# TSEM_R2.net
KiCad netlist of a schematic drawn in EAGLE
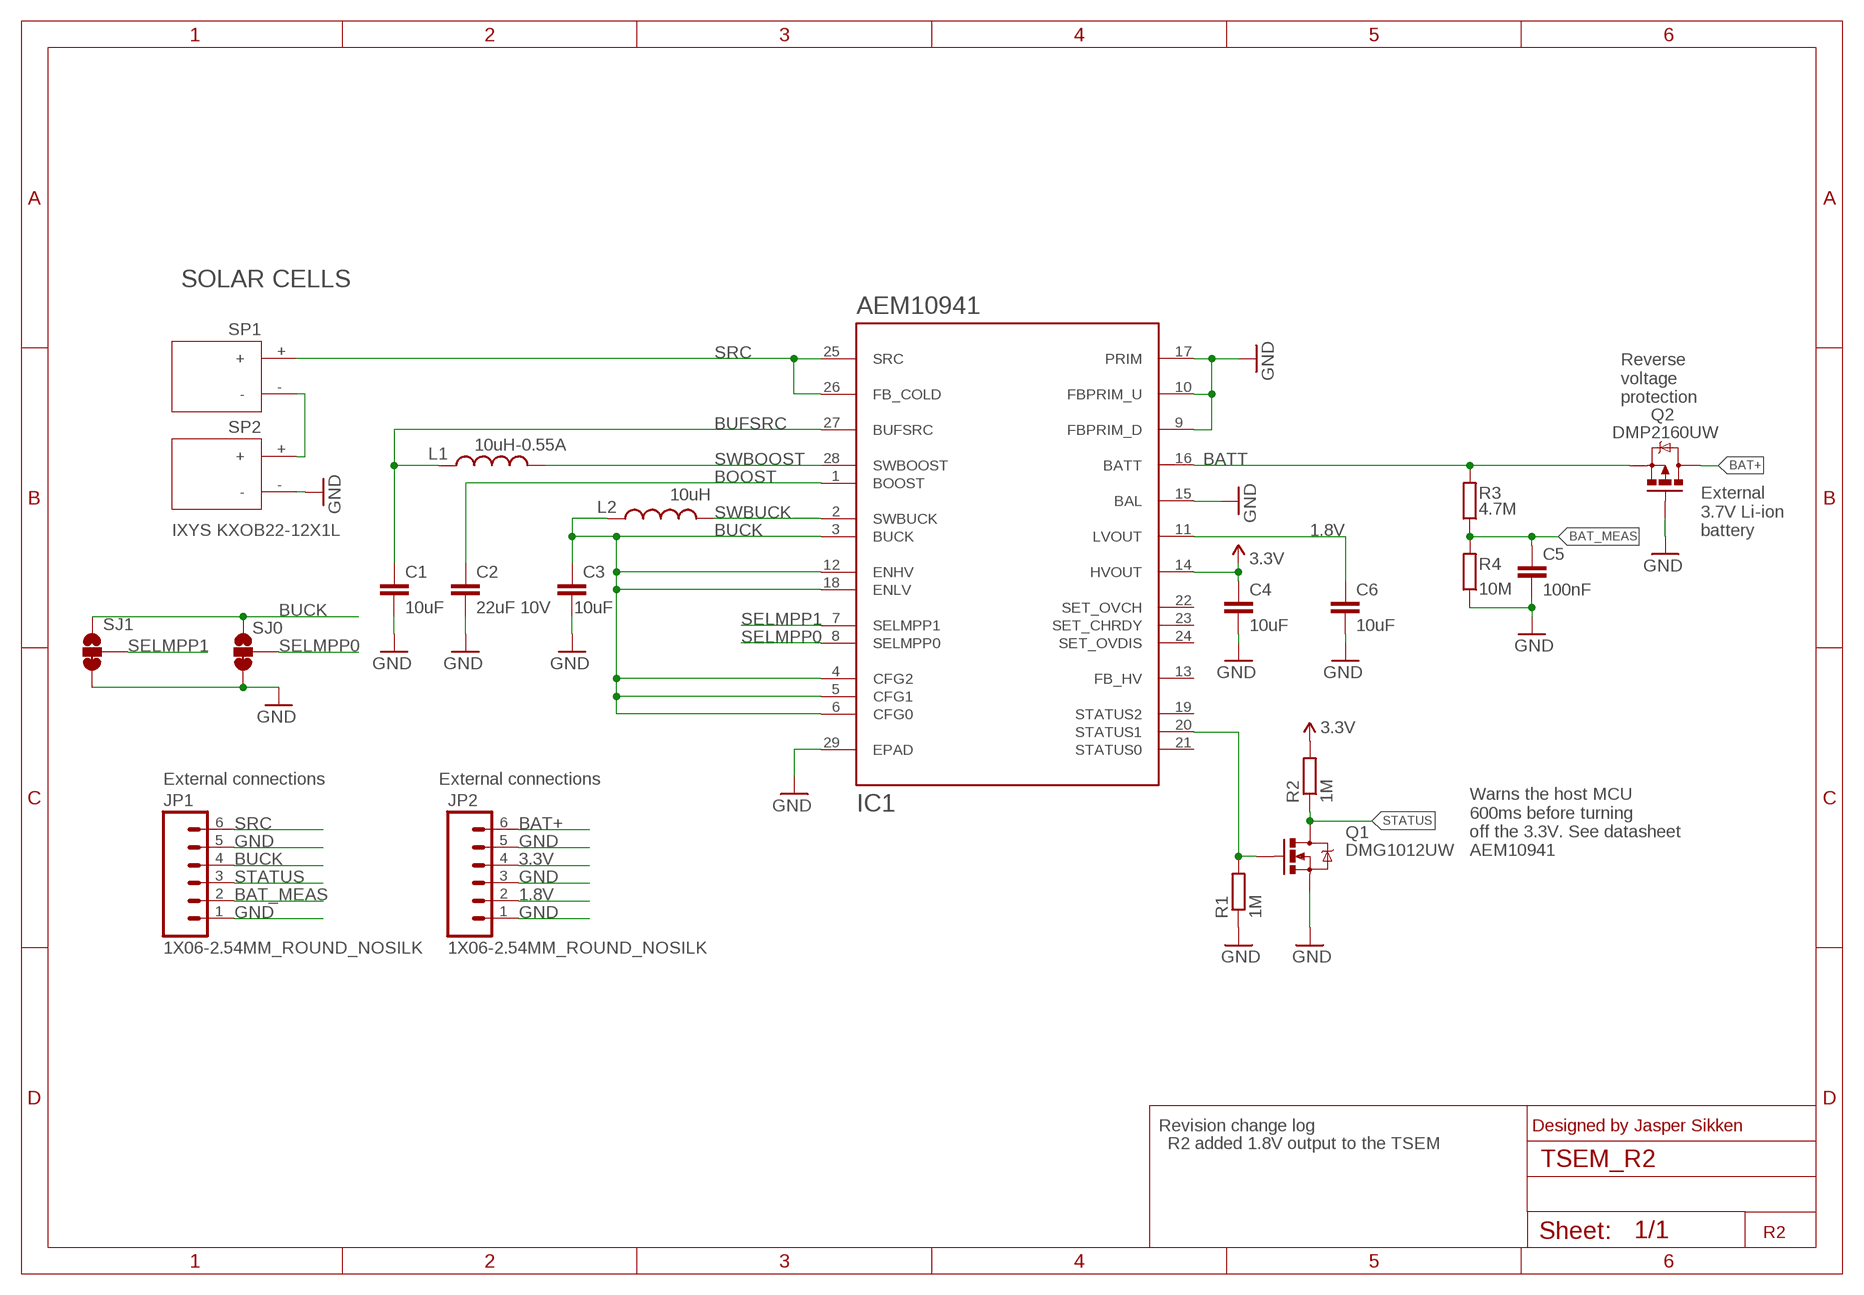
[diagram p0: schematic, sheet 1]

(export (version "E")
  (design (tool "Eeschema 10.0.6"))
  (components
    (comp (ref "C1")
      (value "10uF")
      (footprint "eagle-import:C0603")
      (fields (field (name "MF") "Taiyo Yuden") (field (name "MPN") "LMK107BBJ106MALT"))
      (libsource (lib "eagle-import") (part "C0603_10UF"))
    )
    (comp (ref "C2")
      (value "22uF 10V")
      (footprint "eagle-import:C0603")
      (fields (field (name "MF") "Murata") (field (name "MPN") "GRM188R61A226ME15D"))
      (libsource (lib "eagle-import") (part "C0603_22UF"))
    )
    (comp (ref "C3")
      (value "10uF")
      (footprint "eagle-import:C0603")
      (fields (field (name "MF") "Taiyo Yuden") (field (name "MPN") "LMK107BBJ106MALT"))
      (libsource (lib "eagle-import") (part "C0603_10UF"))
    )
    (comp (ref "C4")
      (value "10uF")
      (footprint "eagle-import:C0603")
      (fields (field (name "MF") "Taiyo Yuden") (field (name "MPN") "LMK107BBJ106MALT"))
      (libsource (lib "eagle-import") (part "C0603_10UF"))
    )
    (comp (ref "C5")
      (value "100nF")
      (footprint "eagle-import:C0402")
      (fields
        (field (name "ALT-PART") "YES")
        (field (name "MF") "Multicomp")
        (field (name "MPN") "MC0402X104K160CT")
      )
      (libsource (lib "eagle-import") (part "C0402_100NF"))
    )
    (comp (ref "C6")
      (value "10uF")
      (footprint "eagle-import:C0603")
      (fields (field (name "MF") "Taiyo Yuden") (field (name "MPN") "LMK107BBJ106MALT"))
      (libsource (lib "eagle-import") (part "C0603_10UF"))
    )
    (comp (ref "IC1")
      (value "AEM10941")
      (footprint "eagle-import:QFN50P505X505X90-28")
      (fields (field (name "MF") "e-peas"))
      (libsource (lib "eagle-import") (part "AEM10941"))
    )
    (comp (ref "JP1")
      (value "1X06-2.54MM_ROUND_NOSILK")
      (footprint "eagle-import:1X06_2.54MM_ROUND_NOSILK")
      (libsource (lib "eagle-import") (part "1X06-2.54MM_ROUND_NOSILK"))
    )
    (comp (ref "JP2")
      (value "1X06-2.54MM_ROUND_NOSILK")
      (footprint "eagle-import:1X06_2.54MM_ROUND_NOSILK")
      (libsource (lib "eagle-import") (part "1X06-2.54MM_ROUND_NOSILK"))
    )
    (comp (ref "L1")
      (value "10uH-0.55A")
      (footprint "eagle-import:LPS4012")
      (fields (field (name "MF") "Coilcraft") (field (name "MPN") "LPS4012-103MRB"))
      (libsource (lib "eagle-import") (part "L3.9X3.9_10UH_0.55A"))
    )
    (comp (ref "L2")
      (value "10uH")
      (footprint "eagle-import:L0603")
      (fields (field (name "MF") "TDK") (field (name "MPN") "MLZ1608M100WT"))
      (libsource (lib "eagle-import") (part "L0603_10UH"))
    )
    (comp (ref "Q1")
      (value "DMG1012UW")
      (footprint "eagle-import:SOT323")
      (fields (field (name "MF") "Diodes") (field (name "MPN") "DMG1012UW-7"))
      (libsource (lib "eagle-import") (part "MOSFET-N-CHANNEL_DMG1012UW"))
    )
    (comp (ref "Q2")
      (value "DMP2160UW")
      (footprint "eagle-import:SOT323")
      (libsource (lib "eagle-import") (part "MOSFET-P-CHANNEL-DMP2160UW"))
    )
    (comp (ref "R1")
      (value "1M")
      (footprint "eagle-import:R0402")
      (fields (field (name "MF") "Walsin") (field (name "MPN") "WR04X1004FTL"))
      (libsource (lib "eagle-import") (part "R0402_1M"))
    )
    (comp (ref "R2")
      (value "1M")
      (footprint "eagle-import:R0402")
      (fields (field (name "MF") "Walsin") (field (name "MPN") "WR04X1004FTL"))
      (libsource (lib "eagle-import") (part "R0402_1M"))
    )
    (comp (ref "R3")
      (value "4.7M")
      (footprint "eagle-import:R0402")
      (fields (field (name "MF") "Multicomp") (field (name "MPN") "MCWR04W4704FTL"))
      (libsource (lib "eagle-import") (part "R0402_4.7M"))
    )
    (comp (ref "R4")
      (value "10M")
      (footprint "eagle-import:R0402")
      (fields (field (name "MF") "Multicomp") (field (name "MPN") "MCWR04X1005FTL"))
      (libsource (lib "eagle-import") (part "R0402_10M"))
    )
    (comp (ref "SJ0")
      (value "SOLDERJUMPER_3WAY_12SHORT3WAY")
      (footprint "eagle-import:SJ_3S_NC_0402")
      (libsource (lib "eagle-import") (part "SOLDERJUMPER_3WAY_12SHORT3WAY"))
    )
    (comp (ref "SJ1")
      (value "SOLDERJUMPER_3WAY_12SHORT3WAY")
      (footprint "eagle-import:SJ_3S_NC_0402")
      (libsource (lib "eagle-import") (part "SOLDERJUMPER_3WAY_12SHORT3WAY"))
    )
    (comp (ref "SP1")
      (value "KXOB22-12X1")
      (footprint "eagle-import:IXYS-KXOB22-12X1")
      (fields (field (name "MF") "IXYS") (field (name "MPN") "IXYS KXOB22-12X1L/F"))
      (libsource (lib "eagle-import") (part "IXYS-KXOB22-12X1"))
    )
    (comp (ref "SP2")
      (value "KXOB22-12X1")
      (footprint "eagle-import:IXYS-KXOB22-12X1")
      (fields (field (name "MF") "IXYS") (field (name "MPN") "IXYS KXOB22-12X1L/F"))
      (libsource (lib "eagle-import") (part "IXYS-KXOB22-12X1"))
    )
  )
  (nets
    (net (code "1") (name "/1.8V") (class "Default")
      (node (ref "C6") (pin "1") (pinfunction "1_1") (pintype "passive"))
      (node (ref "IC1") (pin "11") (pinfunction "LVOUT_11") (pintype "bidirectional"))
      (node (ref "JP2") (pin "2") (pinfunction "2_2") (pintype "passive"))
    )
    (net (code "2") (name "/BATT") (class "Default")
      (node (ref "IC1") (pin "16") (pinfunction "BATT_16") (pintype "bidirectional"))
      (node (ref "Q2") (pin "2") (pinfunction "S_2") (pintype "passive"))
      (node (ref "R3") (pin "2") (pinfunction "2_2") (pintype "passive"))
    )
    (net (code "3") (name "/BOOST") (class "Default")
      (node (ref "C2") (pin "1") (pinfunction "1_1") (pintype "passive"))
      (node (ref "IC1") (pin "1") (pinfunction "BOOST_1") (pintype "bidirectional"))
    )
    (net (code "4") (name "/BUCK") (class "Default")
      (node (ref "C3") (pin "1") (pinfunction "1_1") (pintype "passive"))
      (node (ref "IC1") (pin "12") (pinfunction "ENHV_12") (pintype "bidirectional"))
      (node (ref "IC1") (pin "18") (pinfunction "ENLV_18") (pintype "bidirectional"))
      (node (ref "IC1") (pin "3") (pinfunction "BUCK_3") (pintype "bidirectional"))
      (node (ref "IC1") (pin "4") (pinfunction "CFG2_4") (pintype "bidirectional"))
      (node (ref "IC1") (pin "5") (pinfunction "CFG1_5") (pintype "bidirectional"))
      (node (ref "IC1") (pin "6") (pinfunction "CFG0_6") (pintype "bidirectional"))
      (node (ref "JP1") (pin "4") (pinfunction "4_4") (pintype "passive"))
      (node (ref "L2") (pin "1") (pinfunction "1_1") (pintype "passive"))
      (node (ref "SJ0") (pin "3") (pinfunction "3_3") (pintype "passive"))
      (node (ref "SJ1") (pin "3") (pinfunction "3_3") (pintype "passive"))
    )
    (net (code "5") (name "/BUFSRC") (class "Default")
      (node (ref "C1") (pin "1") (pinfunction "1_1") (pintype "passive"))
      (node (ref "IC1") (pin "27") (pinfunction "BUFSRC_27") (pintype "power_in"))
      (node (ref "L1") (pin "1") (pinfunction "1_1") (pintype "passive"))
    )
    (net (code "6") (name "/SELMPP0") (class "Default")
      (node (ref "IC1") (pin "8") (pinfunction "SELMPP0_8") (pintype "bidirectional"))
      (node (ref "SJ0") (pin "2") (pinfunction "2_2") (pintype "passive"))
    )
    (net (code "7") (name "/SELMPP1") (class "Default")
      (node (ref "IC1") (pin "7") (pinfunction "SELMPP1_7") (pintype "bidirectional"))
      (node (ref "SJ1") (pin "2") (pinfunction "2_2") (pintype "passive"))
    )
    (net (code "8") (name "/SRC") (class "Default")
      (node (ref "IC1") (pin "25") (pinfunction "SRC_25") (pintype "power_in"))
      (node (ref "IC1") (pin "26") (pinfunction "FB_COLD_26") (pintype "input"))
      (node (ref "JP1") (pin "6") (pinfunction "6_6") (pintype "passive"))
      (node (ref "SP1") (pin "+") (pinfunction "+_+") (pintype "bidirectional"))
    )
    (net (code "9") (name "/SWBOOST") (class "Default")
      (node (ref "IC1") (pin "28") (pinfunction "SWBOOST_28") (pintype "power_in"))
      (node (ref "L1") (pin "2") (pinfunction "2_2") (pintype "passive"))
    )
    (net (code "10") (name "/SWBUCK") (class "Default")
      (node (ref "IC1") (pin "2") (pinfunction "SWBUCK_2") (pintype "bidirectional"))
      (node (ref "L2") (pin "2") (pinfunction "2_2") (pintype "passive"))
    )
    (net (code "11") (name "3.3V") (class "Default")
      (node (ref "C4") (pin "1") (pinfunction "1_1") (pintype "passive"))
      (node (ref "IC1") (pin "14") (pinfunction "HVOUT_14") (pintype "bidirectional"))
      (node (ref "JP2") (pin "4") (pinfunction "4_4") (pintype "passive"))
      (node (ref "R2") (pin "2") (pinfunction "2_2") (pintype "passive"))
    )
    (net (code "12") (name "BAT+") (class "Default")
      (node (ref "JP2") (pin "6") (pinfunction "6_6") (pintype "passive"))
      (node (ref "Q2") (pin "3") (pinfunction "D_3") (pintype "passive"))
    )
    (net (code "13") (name "BAT_MEAS") (class "Default")
      (node (ref "C5") (pin "1") (pinfunction "1_1") (pintype "passive"))
      (node (ref "JP1") (pin "2") (pinfunction "2_2") (pintype "passive"))
      (node (ref "R3") (pin "1") (pinfunction "1_1") (pintype "passive"))
      (node (ref "R4") (pin "2") (pinfunction "2_2") (pintype "passive"))
    )
    (net (code "14") (name "GND") (class "Default")
      (node (ref "C1") (pin "2") (pinfunction "2_2") (pintype "passive"))
      (node (ref "C2") (pin "2") (pinfunction "2_2") (pintype "passive"))
      (node (ref "C3") (pin "2") (pinfunction "2_2") (pintype "passive"))
      (node (ref "C4") (pin "2") (pinfunction "2_2") (pintype "passive"))
      (node (ref "C5") (pin "2") (pinfunction "2_2") (pintype "passive"))
      (node (ref "C6") (pin "2") (pinfunction "2_2") (pintype "passive"))
      (node (ref "IC1") (pin "10") (pinfunction "FBPRIM_U_10") (pintype "bidirectional"))
      (node (ref "IC1") (pin "15") (pinfunction "BAL_15") (pintype "bidirectional"))
      (node (ref "IC1") (pin "17") (pinfunction "PRIM_17") (pintype "bidirectional"))
      (node (ref "IC1") (pin "29") (pinfunction "EPAD_29") (pintype "power_in"))
      (node (ref "IC1") (pin "9") (pinfunction "FBPRIM_D_9") (pintype "bidirectional"))
      (node (ref "JP1") (pin "1") (pinfunction "1_1") (pintype "passive"))
      (node (ref "JP1") (pin "5") (pinfunction "5_5") (pintype "passive"))
      (node (ref "JP2") (pin "1") (pinfunction "1_1") (pintype "passive"))
      (node (ref "JP2") (pin "3") (pinfunction "3_3") (pintype "passive"))
      (node (ref "JP2") (pin "5") (pinfunction "5_5") (pintype "passive"))
      (node (ref "Q1") (pin "2") (pinfunction "S_2") (pintype "passive"))
      (node (ref "Q2") (pin "1") (pinfunction "G_1") (pintype "passive"))
      (node (ref "R1") (pin "1") (pinfunction "1_1") (pintype "passive"))
      (node (ref "R4") (pin "1") (pinfunction "1_1") (pintype "passive"))
      (node (ref "SJ0") (pin "1") (pinfunction "1_1") (pintype "passive"))
      (node (ref "SJ1") (pin "1") (pinfunction "1_1") (pintype "passive"))
      (node (ref "SP2") (pin "-") (pinfunction "-_-") (pintype "bidirectional"))
    )
    (net (code "15") (name "Net-(IC1-STATUS1)") (class "Default")
      (node (ref "IC1") (pin "20") (pinfunction "STATUS1_20") (pintype "bidirectional"))
      (node (ref "Q1") (pin "1") (pinfunction "G_1") (pintype "passive"))
      (node (ref "R1") (pin "2") (pinfunction "2_2") (pintype "passive"))
    )
    (net (code "16") (name "Net-(SP1-Pad-)") (class "Default")
      (node (ref "SP1") (pin "-") (pinfunction "-_-") (pintype "bidirectional"))
      (node (ref "SP2") (pin "+") (pinfunction "+_+") (pintype "bidirectional"))
    )
    (net (code "17") (name "STATUS") (class "Default")
      (node (ref "JP1") (pin "3") (pinfunction "3_3") (pintype "passive"))
      (node (ref "Q1") (pin "3") (pinfunction "D_3") (pintype "passive"))
      (node (ref "R2") (pin "1") (pinfunction "1_1") (pintype "passive"))
    )
    (net (code "18") (name "unconnected-(IC1-FB_HV-Pad13)") (class "Default")
      (node (ref "IC1") (pin "13") (pinfunction "FB_HV_13") (pintype "bidirectional"))
    )
    (net (code "19") (name "unconnected-(IC1-SET_CHRDY-Pad23)") (class "Default")
      (node (ref "IC1") (pin "23") (pinfunction "SET_CHRDY_23") (pintype "bidirectional"))
    )
    (net (code "20") (name "unconnected-(IC1-SET_OVCH-Pad22)") (class "Default")
      (node (ref "IC1") (pin "22") (pinfunction "SET_OVCH_22") (pintype "bidirectional"))
    )
    (net (code "21") (name "unconnected-(IC1-SET_OVDIS-Pad24)") (class "Default")
      (node (ref "IC1") (pin "24") (pinfunction "SET_OVDIS_24") (pintype "bidirectional"))
    )
    (net (code "22") (name "unconnected-(IC1-STATUS0-Pad21)") (class "Default")
      (node (ref "IC1") (pin "21") (pinfunction "STATUS0_21") (pintype "bidirectional"))
    )
    (net (code "23") (name "unconnected-(IC1-STATUS2-Pad19)") (class "Default")
      (node (ref "IC1") (pin "19") (pinfunction "STATUS2_19") (pintype "bidirectional"))
    )
  )
)
